# at32.net
KiCad netlist of a schematic drawn in EAGLE
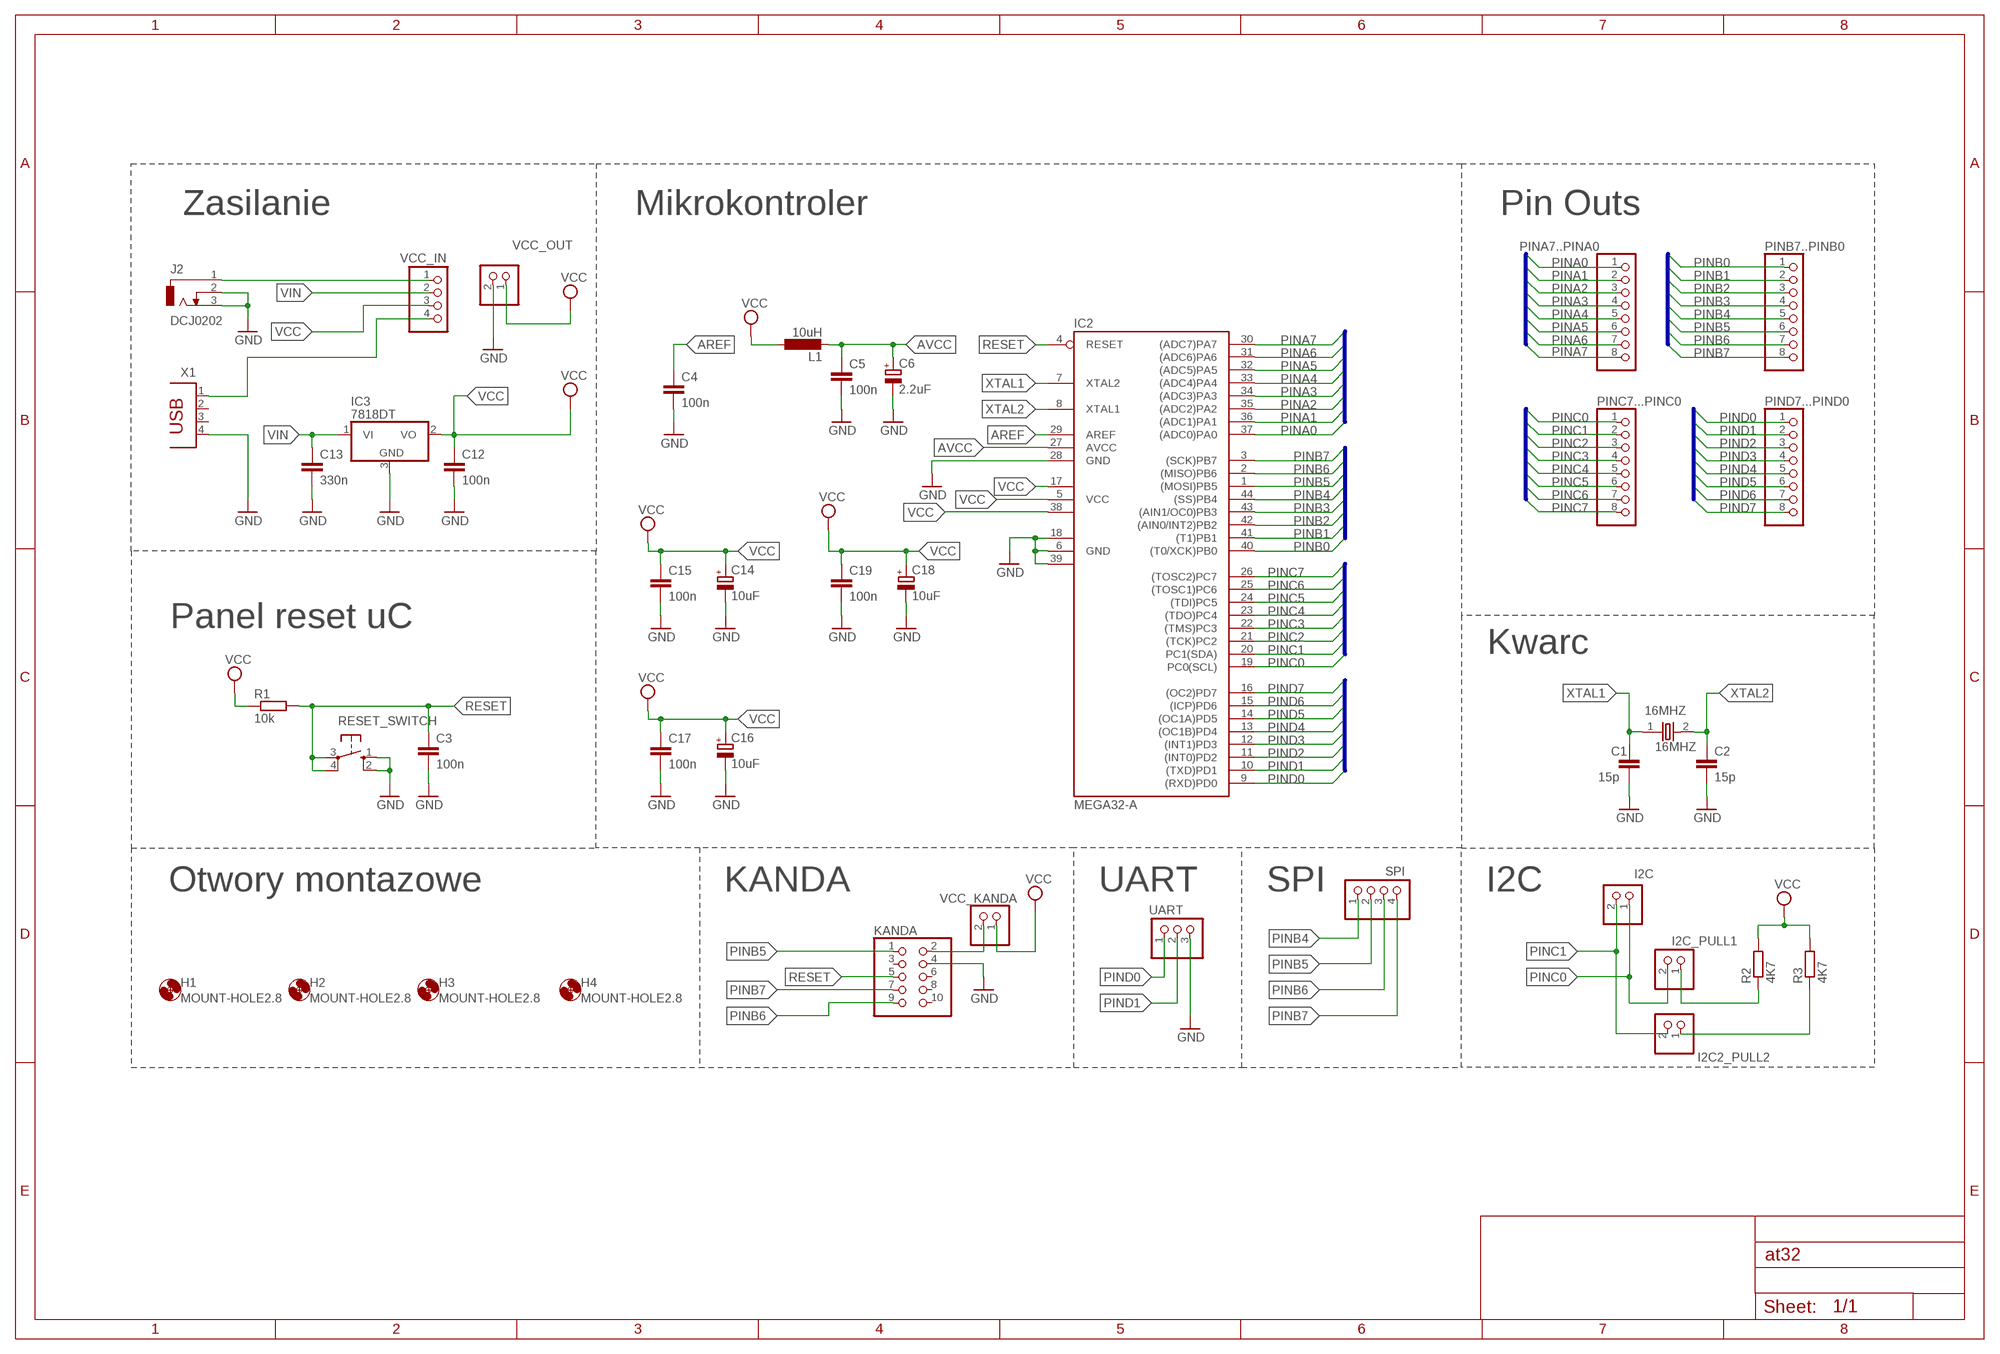
[diagram p0: schematic, sheet 1]

(export (version "E")
  (design (tool "Eeschema 10.0.6"))
  (components
    (comp (ref "16MHZ")
      (value "16MHZ")
      (footprint "eagle-import:HC49SM")
      (libsource (lib "eagle-import") (part "16MHZ"))
    )
    (comp (ref "C1")
      (value "15p")
      (footprint "eagle-import:C1206K")
      (libsource (lib "eagle-import") (part "C-EUC1206K"))
    )
    (comp (ref "C2")
      (value "15p")
      (footprint "eagle-import:C1206K")
      (libsource (lib "eagle-import") (part "C-EUC1206K"))
    )
    (comp (ref "C3")
      (value "100n")
      (footprint "eagle-import:C1206K")
      (libsource (lib "eagle-import") (part "C-EUC1206K"))
    )
    (comp (ref "C4")
      (value "100n")
      (footprint "eagle-import:C1206K")
      (libsource (lib "eagle-import") (part "C-EUC1206K"))
    )
    (comp (ref "C5")
      (value "100n")
      (footprint "eagle-import:C1206K")
      (libsource (lib "eagle-import") (part "C-EUC1206K"))
    )
    (comp (ref "C6")
      (value "2.2uF")
      (footprint "eagle-import:A_3216-18W")
      (libsource (lib "eagle-import") (part "CPOL-EUA/3216-18W"))
    )
    (comp (ref "C12")
      (value "100n")
      (footprint "eagle-import:C1206K")
      (libsource (lib "eagle-import") (part "C-EUC1206K"))
    )
    (comp (ref "C13")
      (value "330n")
      (footprint "eagle-import:C1206K")
      (libsource (lib "eagle-import") (part "C-EUC1206K"))
    )
    (comp (ref "C14")
      (value "10uF")
      (footprint "eagle-import:A_3216-18W")
      (libsource (lib "eagle-import") (part "CPOL-EUA/3216-18W"))
    )
    (comp (ref "C15")
      (value "100n")
      (footprint "eagle-import:C1206K")
      (libsource (lib "eagle-import") (part "C-EUC1206K"))
    )
    (comp (ref "C16")
      (value "10uF")
      (footprint "eagle-import:A_3216-18W")
      (libsource (lib "eagle-import") (part "CPOL-EUA/3216-18W"))
    )
    (comp (ref "C17")
      (value "100n")
      (footprint "eagle-import:C1206K")
      (libsource (lib "eagle-import") (part "C-EUC1206K"))
    )
    (comp (ref "C18")
      (value "10uF")
      (footprint "eagle-import:A_3216-18W")
      (libsource (lib "eagle-import") (part "CPOL-EUA/3216-18W"))
    )
    (comp (ref "C19")
      (value "100n")
      (footprint "eagle-import:C1206K")
      (libsource (lib "eagle-import") (part "C-EUC1206K"))
    )
    (comp (ref "H1")
      (value "MOUNT-HOLE2.8")
      (footprint "eagle-import:2,8")
      (libsource (lib "eagle-import") (part "MOUNT-HOLE2.8"))
    )
    (comp (ref "H2")
      (value "MOUNT-HOLE2.8")
      (footprint "eagle-import:2,8")
      (libsource (lib "eagle-import") (part "MOUNT-HOLE2.8"))
    )
    (comp (ref "H3")
      (value "MOUNT-HOLE2.8")
      (footprint "eagle-import:2,8")
      (libsource (lib "eagle-import") (part "MOUNT-HOLE2.8"))
    )
    (comp (ref "H4")
      (value "MOUNT-HOLE2.8")
      (footprint "eagle-import:2,8")
      (libsource (lib "eagle-import") (part "MOUNT-HOLE2.8"))
    )
    (comp (ref "I2C")
      (value "PINHD-1X2")
      (footprint "eagle-import:1X02")
      (libsource (lib "eagle-import") (part "PINHD-1X2"))
    )
    (comp (ref "I2C2_PULL2")
      (value "PINHD-1X2")
      (footprint "eagle-import:1X02")
      (libsource (lib "eagle-import") (part "PINHD-1X2"))
    )
    (comp (ref "I2C_PULL1")
      (value "PINHD-1X2")
      (footprint "eagle-import:1X02")
      (libsource (lib "eagle-import") (part "PINHD-1X2"))
    )
    (comp (ref "IC2")
      (value "MEGA32-A")
      (footprint "eagle-import:TQFP44")
      (fields (field (name "MPN") "ATMEGA32-16AU"))
      (libsource (lib "eagle-import") (part "MEGA32-A"))
    )
    (comp (ref "IC3")
      (value "7818DT")
      (footprint "eagle-import:TO252")
      (libsource (lib "eagle-import") (part "78DT18"))
    )
    (comp (ref "J2")
      (value "DCJ0202")
      (footprint "eagle-import:DCJ0202")
      (libsource (lib "eagle-import") (part "DCJ0202"))
    )
    (comp (ref "KANDA")
      (value "PINHD-2X5")
      (footprint "eagle-import:2X05")
      (libsource (lib "eagle-import") (part "PINHD-2X5"))
    )
    (comp (ref "L1")
      (value "10uH")
      (footprint "eagle-import:L3225M")
      (libsource (lib "eagle-import") (part "L-EUL3225M"))
    )
    (comp (ref "PINA7..PINA0")
      (value "PINHD-1X8MAT8")
      (footprint "eagle-import:1X08")
      (libsource (lib "eagle-import") (part "PINHD-1X8MAT8"))
    )
    (comp (ref "PINB7..PINB0")
      (value "PINHD-1X8MAT8")
      (footprint "eagle-import:1X08")
      (libsource (lib "eagle-import") (part "PINHD-1X8MAT8"))
    )
    (comp (ref "PINC7...PINC0")
      (value "PINHD-1X8MAT8")
      (footprint "eagle-import:1X08")
      (libsource (lib "eagle-import") (part "PINHD-1X8MAT8"))
    )
    (comp (ref "PIND7...PIND0")
      (value "PINHD-1X8MAT8")
      (footprint "eagle-import:1X08")
      (libsource (lib "eagle-import") (part "PINHD-1X8MAT8"))
    )
    (comp (ref "R1")
      (value "10k")
      (footprint "eagle-import:R3216")
      (libsource (lib "eagle-import") (part "R-EU_R3216"))
    )
    (comp (ref "R2")
      (value "4K7")
      (footprint "eagle-import:R3216")
      (libsource (lib "eagle-import") (part "R-EU_R3216"))
    )
    (comp (ref "R3")
      (value "4K7")
      (footprint "eagle-import:R3216")
      (libsource (lib "eagle-import") (part "R-EU_R3216"))
    )
    (comp (ref "RESET_SWITCH")
      (value "10-XX")
      (footprint "eagle-import:B3F-10XX")
      (fields (field (name "MPN") "B3F-1000"))
      (libsource (lib "eagle-import") (part "10-XX"))
    )
    (comp (ref "SPI")
      (value "PINHD-1X4")
      (footprint "eagle-import:1X04")
      (libsource (lib "eagle-import") (part "PINHD-1X4"))
    )
    (comp (ref "UART")
      (value "PINHD-1X3")
      (footprint "eagle-import:1X03")
      (libsource (lib "eagle-import") (part "PINHD-1X3"))
    )
    (comp (ref "VCC_IN")
      (value "PINHD-1X4")
      (footprint "eagle-import:1X04")
      (libsource (lib "eagle-import") (part "PINHD-1X4"))
    )
    (comp (ref "VCC_KANDA")
      (value "PINHD-1X2")
      (footprint "eagle-import:1X02")
      (libsource (lib "eagle-import") (part "PINHD-1X2"))
    )
    (comp (ref "VCC_OUT")
      (value "PINHD-1X2")
      (footprint "eagle-import:1X02")
      (libsource (lib "eagle-import") (part "PINHD-1X2"))
    )
    (comp (ref "X1")
      (value "PN87520")
      (footprint "eagle-import:PN87520")
      (libsource (lib "eagle-import") (part "PN87520"))
    )
  )
  (nets
    (net (code "1") (name "/PINA0") (class "Default")
      (node (ref "IC2") (pin "37") (pinfunction "(ADC0)PA0_37") (pintype "bidirectional"))
      (node (ref "PINA7..PINA0") (pin "1") (pinfunction "1_1") (pintype "passive"))
    )
    (net (code "2") (name "/PINA1") (class "Default")
      (node (ref "IC2") (pin "36") (pinfunction "(ADC1)PA1_36") (pintype "bidirectional"))
      (node (ref "PINA7..PINA0") (pin "2") (pinfunction "2_2") (pintype "passive"))
    )
    (net (code "3") (name "/PINA2") (class "Default")
      (node (ref "IC2") (pin "35") (pinfunction "(ADC2)PA2_35") (pintype "bidirectional"))
      (node (ref "PINA7..PINA0") (pin "3") (pinfunction "3_3") (pintype "passive"))
    )
    (net (code "4") (name "/PINA3") (class "Default")
      (node (ref "IC2") (pin "34") (pinfunction "(ADC3)PA3_34") (pintype "bidirectional"))
      (node (ref "PINA7..PINA0") (pin "4") (pinfunction "4_4") (pintype "passive"))
    )
    (net (code "5") (name "/PINA4") (class "Default")
      (node (ref "IC2") (pin "33") (pinfunction "(ADC4)PA4_33") (pintype "bidirectional"))
      (node (ref "PINA7..PINA0") (pin "5") (pinfunction "5_5") (pintype "passive"))
    )
    (net (code "6") (name "/PINA5") (class "Default")
      (node (ref "IC2") (pin "32") (pinfunction "(ADC5)PA5_32") (pintype "bidirectional"))
      (node (ref "PINA7..PINA0") (pin "6") (pinfunction "6_6") (pintype "passive"))
    )
    (net (code "7") (name "/PINA6") (class "Default")
      (node (ref "IC2") (pin "31") (pinfunction "(ADC6)PA6_31") (pintype "bidirectional"))
      (node (ref "PINA7..PINA0") (pin "7") (pinfunction "7_7") (pintype "passive"))
    )
    (net (code "8") (name "/PINA7") (class "Default")
      (node (ref "IC2") (pin "30") (pinfunction "(ADC7)PA7_30") (pintype "bidirectional"))
      (node (ref "PINA7..PINA0") (pin "8") (pinfunction "8_8") (pintype "passive"))
    )
    (net (code "9") (name "/PINB0") (class "Default")
      (node (ref "IC2") (pin "40") (pinfunction "(T0/XCK)PB0_40") (pintype "bidirectional"))
      (node (ref "PINB7..PINB0") (pin "1") (pinfunction "1_1") (pintype "passive"))
    )
    (net (code "10") (name "/PINB1") (class "Default")
      (node (ref "IC2") (pin "41") (pinfunction "(T1)PB1_41") (pintype "bidirectional"))
      (node (ref "PINB7..PINB0") (pin "2") (pinfunction "2_2") (pintype "passive"))
    )
    (net (code "11") (name "/PINB2") (class "Default")
      (node (ref "IC2") (pin "42") (pinfunction "(AIN0/INT2)PB2_42") (pintype "bidirectional"))
      (node (ref "PINB7..PINB0") (pin "3") (pinfunction "3_3") (pintype "passive"))
    )
    (net (code "12") (name "/PINB3") (class "Default")
      (node (ref "IC2") (pin "43") (pinfunction "(AIN1/OC0)PB3_43") (pintype "bidirectional"))
      (node (ref "PINB7..PINB0") (pin "4") (pinfunction "4_4") (pintype "passive"))
    )
    (net (code "13") (name "/PINC2") (class "Default")
      (node (ref "IC2") (pin "21") (pinfunction "(TCK)PC2_21") (pintype "bidirectional"))
      (node (ref "PINC7...PINC0") (pin "3") (pinfunction "3_3") (pintype "passive"))
    )
    (net (code "14") (name "/PINC3") (class "Default")
      (node (ref "IC2") (pin "22") (pinfunction "(TMS)PC3_22") (pintype "bidirectional"))
      (node (ref "PINC7...PINC0") (pin "4") (pinfunction "4_4") (pintype "passive"))
    )
    (net (code "15") (name "/PINC4") (class "Default")
      (node (ref "IC2") (pin "23") (pinfunction "(TDO)PC4_23") (pintype "bidirectional"))
      (node (ref "PINC7...PINC0") (pin "5") (pinfunction "5_5") (pintype "passive"))
    )
    (net (code "16") (name "/PINC5") (class "Default")
      (node (ref "IC2") (pin "24") (pinfunction "(TDI)PC5_24") (pintype "bidirectional"))
      (node (ref "PINC7...PINC0") (pin "6") (pinfunction "6_6") (pintype "passive"))
    )
    (net (code "17") (name "/PINC6") (class "Default")
      (node (ref "IC2") (pin "25") (pinfunction "(TOSC1)PC6_25") (pintype "bidirectional"))
      (node (ref "PINC7...PINC0") (pin "7") (pinfunction "7_7") (pintype "passive"))
    )
    (net (code "18") (name "/PINC7") (class "Default")
      (node (ref "IC2") (pin "26") (pinfunction "(TOSC2)PC7_26") (pintype "bidirectional"))
      (node (ref "PINC7...PINC0") (pin "8") (pinfunction "8_8") (pintype "passive"))
    )
    (net (code "19") (name "/PIND2") (class "Default")
      (node (ref "IC2") (pin "11") (pinfunction "(INT0)PD2_11") (pintype "bidirectional"))
      (node (ref "PIND7...PIND0") (pin "3") (pinfunction "3_3") (pintype "passive"))
    )
    (net (code "20") (name "/PIND3") (class "Default")
      (node (ref "IC2") (pin "12") (pinfunction "(INT1)PD3_12") (pintype "bidirectional"))
      (node (ref "PIND7...PIND0") (pin "4") (pinfunction "4_4") (pintype "passive"))
    )
    (net (code "21") (name "/PIND4") (class "Default")
      (node (ref "IC2") (pin "13") (pinfunction "(OC1B)PD4_13") (pintype "bidirectional"))
      (node (ref "PIND7...PIND0") (pin "5") (pinfunction "5_5") (pintype "passive"))
    )
    (net (code "22") (name "/PIND5") (class "Default")
      (node (ref "IC2") (pin "14") (pinfunction "(OC1A)PD5_14") (pintype "bidirectional"))
      (node (ref "PIND7...PIND0") (pin "6") (pinfunction "6_6") (pintype "passive"))
    )
    (net (code "23") (name "/PIND6") (class "Default")
      (node (ref "IC2") (pin "15") (pinfunction "(ICP)PD6_15") (pintype "bidirectional"))
      (node (ref "PIND7...PIND0") (pin "7") (pinfunction "7_7") (pintype "passive"))
    )
    (net (code "24") (name "/PIND7") (class "Default")
      (node (ref "IC2") (pin "16") (pinfunction "(OC2)PD7_16") (pintype "bidirectional"))
      (node (ref "PIND7...PIND0") (pin "8") (pinfunction "8_8") (pintype "passive"))
    )
    (net (code "25") (name "AREF") (class "Default")
      (node (ref "C4") (pin "1") (pinfunction "1_1") (pintype "passive"))
      (node (ref "IC2") (pin "29") (pinfunction "AREF_29") (pintype "passive"))
    )
    (net (code "26") (name "AVCC") (class "Default")
      (node (ref "C5") (pin "1") (pinfunction "1_1") (pintype "passive"))
      (node (ref "C6") (pin "+") (pinfunction "+_+") (pintype "passive"))
      (node (ref "IC2") (pin "27") (pinfunction "AVCC_27") (pintype "power_in"))
      (node (ref "L1") (pin "2") (pinfunction "2_2") (pintype "passive"))
    )
    (net (code "27") (name "GND") (class "Default")
      (node (ref "C1") (pin "2") (pinfunction "2_2") (pintype "passive"))
      (node (ref "C12") (pin "2") (pinfunction "2_2") (pintype "passive"))
      (node (ref "C13") (pin "2") (pinfunction "2_2") (pintype "passive"))
      (node (ref "C14") (pin "-") (pinfunction "-_-") (pintype "passive"))
      (node (ref "C15") (pin "2") (pinfunction "2_2") (pintype "passive"))
      (node (ref "C16") (pin "-") (pinfunction "-_-") (pintype "passive"))
      (node (ref "C17") (pin "2") (pinfunction "2_2") (pintype "passive"))
      (node (ref "C18") (pin "-") (pinfunction "-_-") (pintype "passive"))
      (node (ref "C19") (pin "2") (pinfunction "2_2") (pintype "passive"))
      (node (ref "C2") (pin "2") (pinfunction "2_2") (pintype "passive"))
      (node (ref "C3") (pin "2") (pinfunction "2_2") (pintype "passive"))
      (node (ref "C4") (pin "2") (pinfunction "2_2") (pintype "passive"))
      (node (ref "C5") (pin "2") (pinfunction "2_2") (pintype "passive"))
      (node (ref "C6") (pin "-") (pinfunction "-_-") (pintype "passive"))
      (node (ref "IC2") (pin "18") (pinfunction "GND1_18") (pintype "power_in"))
      (node (ref "IC2") (pin "28") (pinfunction "GND_28") (pintype "power_in"))
      (node (ref "IC2") (pin "39") (pinfunction "GND2_39") (pintype "power_in"))
      (node (ref "IC2") (pin "6") (pinfunction "GND_6") (pintype "power_in"))
      (node (ref "IC3") (pin "3") (pinfunction "GND_3") (pintype "passive"))
      (node (ref "J2") (pin "2") (pinfunction "2_2") (pintype "passive"))
      (node (ref "J2") (pin "3") (pinfunction "3_3") (pintype "passive"))
      (node (ref "KANDA") (pin "4") (pinfunction "4_4") (pintype "passive"))
      (node (ref "RESET_SWITCH") (pin "1") (pinfunction "S_1") (pintype "passive"))
      (node (ref "RESET_SWITCH") (pin "2") (pinfunction "S1_2") (pintype "passive"))
      (node (ref "UART") (pin "3") (pinfunction "3_3") (pintype "passive"))
      (node (ref "VCC_OUT") (pin "2") (pinfunction "1_2") (pintype "passive"))
      (node (ref "X1") (pin "4") (pinfunction "4_4") (pintype "passive"))
    )
    (net (code "28") (name "Net-(I2C2_PULL2-2)") (class "Default")
      (node (ref "I2C2_PULL2") (pin "1") (pinfunction "2_1") (pintype "passive"))
      (node (ref "R3") (pin "1") (pinfunction "1_1") (pintype "passive"))
    )
    (net (code "29") (name "Net-(I2C_PULL1-2)") (class "Default")
      (node (ref "I2C_PULL1") (pin "1") (pinfunction "2_1") (pintype "passive"))
      (node (ref "R2") (pin "1") (pinfunction "1_1") (pintype "passive"))
    )
    (net (code "30") (name "Net-(J2-Pad1)") (class "Default")
      (node (ref "J2") (pin "1") (pinfunction "1_1") (pintype "passive"))
      (node (ref "VCC_IN") (pin "1") (pinfunction "1_1") (pintype "passive"))
    )
    (net (code "31") (name "Net-(VCC_IN-Pad4)") (class "Default")
      (node (ref "VCC_IN") (pin "4") (pinfunction "4_4") (pintype "passive"))
      (node (ref "X1") (pin "1") (pinfunction "1_1") (pintype "passive"))
    )
    (net (code "32") (name "Net-(VCC_KANDA-1)") (class "Default")
      (node (ref "KANDA") (pin "2") (pinfunction "2_2") (pintype "passive"))
      (node (ref "VCC_KANDA") (pin "2") (pinfunction "1_2") (pintype "passive"))
    )
    (net (code "33") (name "PINB4") (class "Default")
      (node (ref "IC2") (pin "44") (pinfunction "(SS)PB4_44") (pintype "bidirectional"))
      (node (ref "PINB7..PINB0") (pin "5") (pinfunction "5_5") (pintype "passive"))
      (node (ref "SPI") (pin "1") (pinfunction "1_1") (pintype "passive"))
    )
    (net (code "34") (name "PINB5") (class "Default")
      (node (ref "IC2") (pin "1") (pinfunction "(MOSI)PB5_1") (pintype "bidirectional"))
      (node (ref "KANDA") (pin "1") (pinfunction "1_1") (pintype "passive"))
      (node (ref "PINB7..PINB0") (pin "6") (pinfunction "6_6") (pintype "passive"))
      (node (ref "SPI") (pin "2") (pinfunction "2_2") (pintype "passive"))
    )
    (net (code "35") (name "PINB6") (class "Default")
      (node (ref "IC2") (pin "2") (pinfunction "(MISO)PB6_2") (pintype "bidirectional"))
      (node (ref "KANDA") (pin "9") (pinfunction "9_9") (pintype "passive"))
      (node (ref "PINB7..PINB0") (pin "7") (pinfunction "7_7") (pintype "passive"))
      (node (ref "SPI") (pin "3") (pinfunction "3_3") (pintype "passive"))
    )
    (net (code "36") (name "PINB7") (class "Default")
      (node (ref "IC2") (pin "3") (pinfunction "(SCK)PB7_3") (pintype "bidirectional"))
      (node (ref "KANDA") (pin "7") (pinfunction "7_7") (pintype "passive"))
      (node (ref "PINB7..PINB0") (pin "8") (pinfunction "8_8") (pintype "passive"))
      (node (ref "SPI") (pin "4") (pinfunction "4_4") (pintype "passive"))
    )
    (net (code "37") (name "PINC0") (class "Default")
      (node (ref "I2C") (pin "1") (pinfunction "2_1") (pintype "passive"))
      (node (ref "I2C_PULL1") (pin "2") (pinfunction "1_2") (pintype "passive"))
      (node (ref "IC2") (pin "19") (pinfunction "PC0(SCL)_19") (pintype "bidirectional"))
      (node (ref "PINC7...PINC0") (pin "1") (pinfunction "1_1") (pintype "passive"))
    )
    (net (code "38") (name "PINC1") (class "Default")
      (node (ref "I2C") (pin "2") (pinfunction "1_2") (pintype "passive"))
      (node (ref "I2C2_PULL2") (pin "2") (pinfunction "1_2") (pintype "passive"))
      (node (ref "IC2") (pin "20") (pinfunction "PC1(SDA)_20") (pintype "bidirectional"))
      (node (ref "PINC7...PINC0") (pin "2") (pinfunction "2_2") (pintype "passive"))
    )
    (net (code "39") (name "PIND0") (class "Default")
      (node (ref "IC2") (pin "9") (pinfunction "(RXD)PD0_9") (pintype "bidirectional"))
      (node (ref "PIND7...PIND0") (pin "1") (pinfunction "1_1") (pintype "passive"))
      (node (ref "UART") (pin "1") (pinfunction "1_1") (pintype "passive"))
    )
    (net (code "40") (name "PIND1") (class "Default")
      (node (ref "IC2") (pin "10") (pinfunction "(TXD)PD1_10") (pintype "bidirectional"))
      (node (ref "PIND7...PIND0") (pin "2") (pinfunction "2_2") (pintype "passive"))
      (node (ref "UART") (pin "2") (pinfunction "2_2") (pintype "passive"))
    )
    (net (code "41") (name "RESET") (class "Default")
      (node (ref "C3") (pin "1") (pinfunction "1_1") (pintype "passive"))
      (node (ref "IC2") (pin "4") (pinfunction "RESET_4") (pintype "input"))
      (node (ref "KANDA") (pin "5") (pinfunction "5_5") (pintype "passive"))
      (node (ref "R1") (pin "2") (pinfunction "2_2") (pintype "passive"))
      (node (ref "RESET_SWITCH") (pin "3") (pinfunction "P_3") (pintype "passive"))
      (node (ref "RESET_SWITCH") (pin "4") (pinfunction "P1_4") (pintype "passive"))
    )
    (net (code "42") (name "VCC") (class "Default")
      (node (ref "C12") (pin "1") (pinfunction "1_1") (pintype "passive"))
      (node (ref "C14") (pin "+") (pinfunction "+_+") (pintype "passive"))
      (node (ref "C15") (pin "1") (pinfunction "1_1") (pintype "passive"))
      (node (ref "C16") (pin "+") (pinfunction "+_+") (pintype "passive"))
      (node (ref "C17") (pin "1") (pinfunction "1_1") (pintype "passive"))
      (node (ref "C18") (pin "+") (pinfunction "+_+") (pintype "passive"))
      (node (ref "C19") (pin "1") (pinfunction "1_1") (pintype "passive"))
      (node (ref "IC2") (pin "17") (pinfunction "VCC1_17") (pintype "power_in"))
      (node (ref "IC2") (pin "38") (pinfunction "VCC2_38") (pintype "power_in"))
      (node (ref "IC2") (pin "5") (pinfunction "VCC_5") (pintype "power_in"))
      (node (ref "IC3") (pin "2") (pinfunction "VO_2") (pintype "passive"))
      (node (ref "L1") (pin "1") (pinfunction "1_1") (pintype "passive"))
      (node (ref "R1") (pin "1") (pinfunction "1_1") (pintype "passive"))
      (node (ref "R2") (pin "2") (pinfunction "2_2") (pintype "passive"))
      (node (ref "R3") (pin "2") (pinfunction "2_2") (pintype "passive"))
      (node (ref "VCC_IN") (pin "3") (pinfunction "3_3") (pintype "passive"))
      (node (ref "VCC_KANDA") (pin "1") (pinfunction "2_1") (pintype "passive"))
      (node (ref "VCC_OUT") (pin "1") (pinfunction "2_1") (pintype "passive"))
    )
    (net (code "43") (name "VIN") (class "Default")
      (node (ref "C13") (pin "1") (pinfunction "1_1") (pintype "passive"))
      (node (ref "IC3") (pin "1") (pinfunction "VI_1") (pintype "input"))
      (node (ref "VCC_IN") (pin "2") (pinfunction "2_2") (pintype "passive"))
    )
    (net (code "44") (name "XTAL1") (class "Default")
      (node (ref "16MHZ") (pin "1") (pinfunction "1_1") (pintype "passive"))
      (node (ref "C1") (pin "1") (pinfunction "1_1") (pintype "passive"))
      (node (ref "IC2") (pin "7") (pinfunction "XTAL2_7") (pintype "bidirectional"))
    )
    (net (code "45") (name "XTAL2") (class "Default")
      (node (ref "16MHZ") (pin "2") (pinfunction "2_2") (pintype "passive"))
      (node (ref "C2") (pin "1") (pinfunction "1_1") (pintype "passive"))
      (node (ref "IC2") (pin "8") (pinfunction "XTAL1_8") (pintype "bidirectional"))
    )
    (net (code "46") (name "unconnected-(KANDA-Pad3)") (class "Default")
      (node (ref "KANDA") (pin "3") (pinfunction "3_3") (pintype "passive"))
    )
    (net (code "47") (name "unconnected-(KANDA-Pad6)") (class "Default")
      (node (ref "KANDA") (pin "6") (pinfunction "6_6") (pintype "passive"))
    )
    (net (code "48") (name "unconnected-(KANDA-Pad8)") (class "Default")
      (node (ref "KANDA") (pin "8") (pinfunction "8_8") (pintype "passive"))
    )
    (net (code "49") (name "unconnected-(KANDA-Pad10)") (class "Default")
      (node (ref "KANDA") (pin "10") (pinfunction "10_10") (pintype "passive"))
    )
    (net (code "50") (name "unconnected-(X1-Pad2)") (class "Default")
      (node (ref "X1") (pin "2") (pinfunction "2_2") (pintype "passive"))
    )
    (net (code "51") (name "unconnected-(X1-Pad3)") (class "Default")
      (node (ref "X1") (pin "3") (pinfunction "3_3") (pintype "passive"))
    )
  )
)
